# Power.net
KiCad netlist of a schematic drawn in Altium Designer
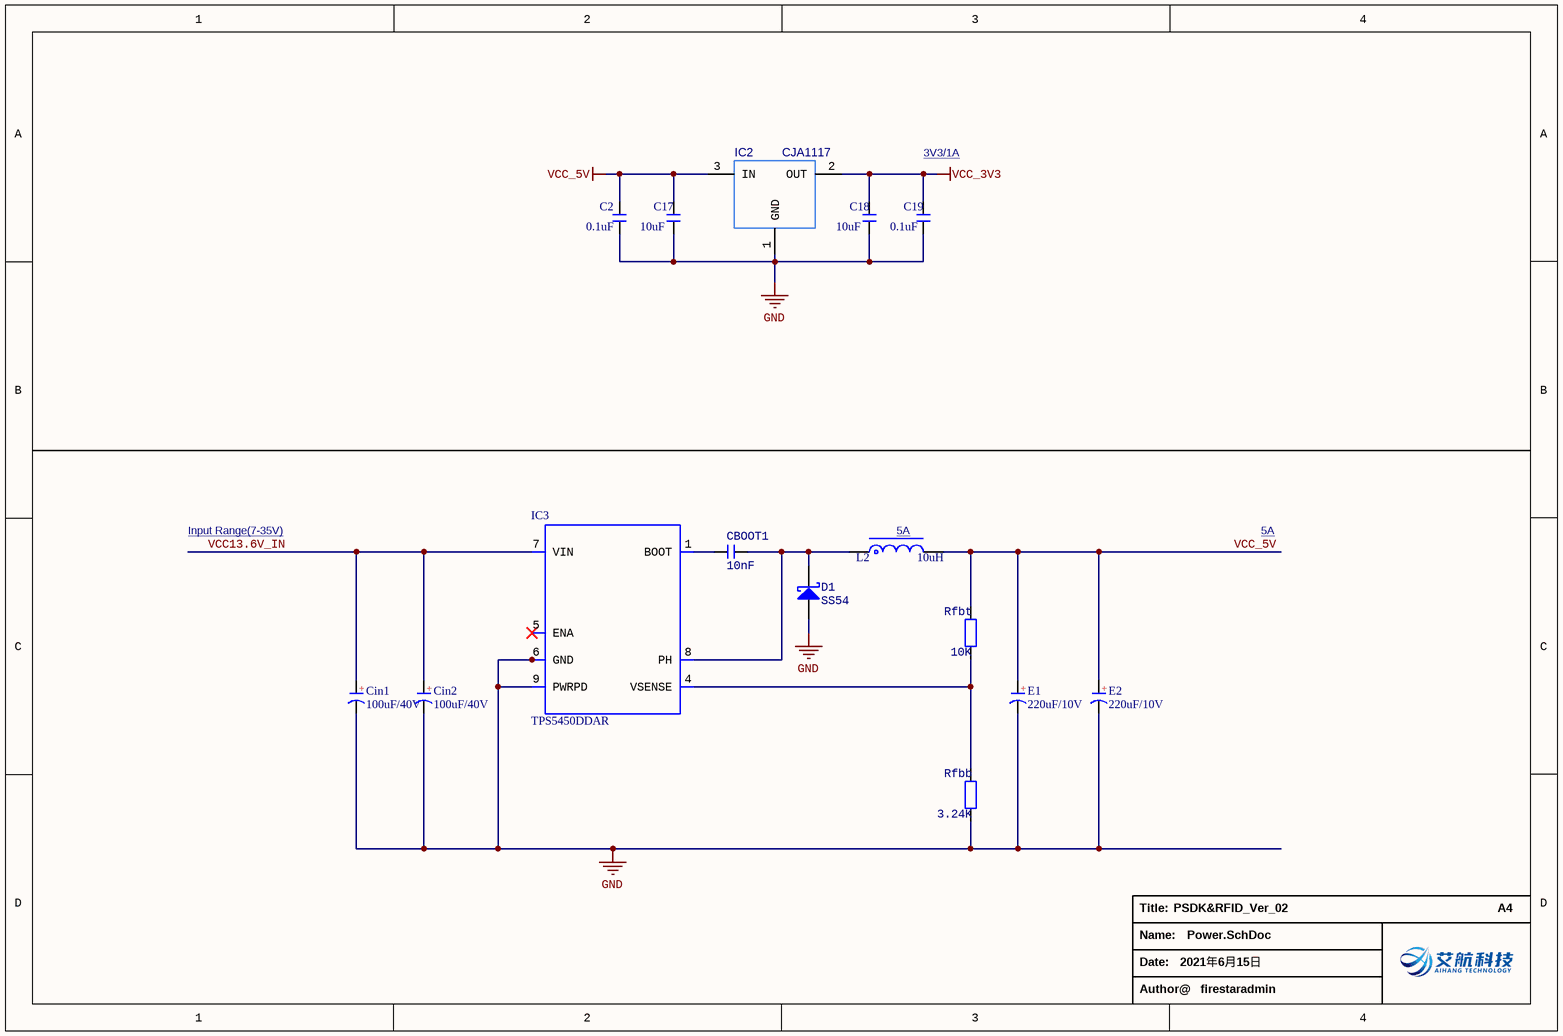
[diagram p0: Power.SchDoc]

(export (version "E")
  (design (tool "Eeschema 10.0.6"))
  (components
    (comp (ref "C2")
      (value "0.1uF")
      (footprint "C 0603_L")
      (description "无极性贴片电容")
      (fields (field (name "版权归属") "源创客"))
      (libsource (lib "altium-import") (part "root_1_C_"))
    )
    (comp (ref "C17")
      (value "10uF")
      (footprint "C 0805_L")
      (description "无极性贴片电容")
      (fields (field (name "版权归属") "源创客"))
      (libsource (lib "altium-import") (part "root_1_C_"))
    )
    (comp (ref "C18")
      (value "10uF")
      (footprint "C 0805_L")
      (description "无极性贴片电容")
      (fields (field (name "版权归属") "源创客"))
      (libsource (lib "altium-import") (part "root_1_C_"))
    )
    (comp (ref "C19")
      (value "0.1uF")
      (footprint "C 0603_L")
      (description "无极性贴片电容")
      (fields (field (name "版权归属") "源创客"))
      (libsource (lib "altium-import") (part "root_1_C_"))
    )
    (comp (ref "CBOOT1")
      (value "10nF")
      (footprint "C 0603_L")
      (description "无极性贴片电容")
      (fields (field (name "版权归属") "源创客"))
      (libsource (lib "SCH-电阻-电容-电感") (part "C"))
    )
    (comp (ref "Cin1")
      (value "100uF/40V")
      (footprint "CM D(6.3*7.7)")
      (description "贴片电解电容")
      (fields (field (name "版权归属") "源创客"))
      (libsource (lib "SCH-电阻-电容-电感") (part "C-CM"))
    )
    (comp (ref "Cin2")
      (value "100uF/40V")
      (footprint "CM D(6.3*7.7)")
      (description "贴片电解电容")
      (fields (field (name "版权归属") "源创客"))
      (libsource (lib "SCH-电阻-电容-电感") (part "C-CM"))
    )
    (comp (ref "D1")
      (value "SS54")
      (footprint "SMC")
      (description "肖特基二极管")
      (libsource (lib "SCH-二极管-整流桥") (part "SS54"))
    )
    (comp (ref "E1")
      (value "220uF/10V")
      (footprint "CD D(7343)")
      (description "贴片钽电容")
      (fields (field (name "版权归属") "源创客"))
      (libsource (lib "SCH-电阻-电容-电感") (part "C-CD"))
    )
    (comp (ref "E2")
      (value "220uF/10V")
      (footprint "CD D(7343)")
      (description "贴片钽电容")
      (fields (field (name "版权归属") "源创客"))
      (libsource (lib "SCH-电阻-电容-电感") (part "C-CD"))
    )
    (comp (ref "IC2")
      (value "CJA1117")
      (footprint "SOT89_M")
      (description "线性稳压器(LDO) SOT89  CJA1117B-3.3 : 最大输入电压  15V ; 3.3V @ 1A")
      (libsource (lib "SCH-电源类芯片") (part "CJA1117"))
    )
    (comp (ref "IC3")
      (value "TPS5450")
      (footprint "ESOP8_N")
      (fields
        (field (name "MANUFACTURER PART NUMBER") "TPS5450DDA")
        (field (name "PACKAGEREFERENCE") "TPS5450DDAR")
      )
      (libsource (lib "SCH-电源类芯片") (part "TPS5450"))
    )
    (comp (ref "L2")
      (value "10uH")
      (footprint "L-SMD-1040")
      (description "贴片功率电感")
      (fields (field (name "版权归属") "源创客"))
      (libsource (lib "SCH-电阻-电容-电感") (part "L-CD"))
    )
    (comp (ref "Rfbb")
      (value "3.24K")
      (footprint "R 0603_L")
      (description "贴片电阻")
      (fields (field (name "版权归属") "源创客"))
      (libsource (lib "SCH-电阻-电容-电感") (part "R"))
    )
    (comp (ref "Rfbt")
      (value "10K")
      (footprint "R 0603_L")
      (description "贴片电阻")
      (fields (field (name "版权归属") "源创客"))
      (libsource (lib "SCH-电阻-电容-电感") (part "R"))
    )
  )
  (nets
    (net (code "1") (name "/VCC13.6V_IN") (class "Default")
      (node (ref "Cin1") (pin "1") (pinfunction "A_1") (pintype "passive"))
      (node (ref "Cin2") (pin "1") (pinfunction "A_1") (pintype "passive"))
      (node (ref "IC3") (pin "7") (pinfunction "VIN_7") (pintype "passive"))
    )
    (net (code "2") (name "GND") (class "Default")
      (node (ref "C17") (pin "1") (pinfunction "1_1") (pintype "passive"))
      (node (ref "C18") (pin "1") (pinfunction "1_1") (pintype "passive"))
      (node (ref "C19") (pin "1") (pinfunction "1_1") (pintype "passive"))
      (node (ref "C2") (pin "1") (pinfunction "1_1") (pintype "passive"))
      (node (ref "Cin1") (pin "2") (pinfunction "K_2") (pintype "passive"))
      (node (ref "Cin2") (pin "2") (pinfunction "K_2") (pintype "passive"))
      (node (ref "D1") (pin "1") (pinfunction "A_1") (pintype "passive"))
      (node (ref "E1") (pin "2") (pinfunction "K_2") (pintype "passive"))
      (node (ref "E2") (pin "2") (pinfunction "K_2") (pintype "passive"))
      (node (ref "IC2") (pin "1") (pinfunction "GND_1") (pintype "passive"))
      (node (ref "IC3") (pin "2") (pinfunction "NC_2") (pintype "passive"))
      (node (ref "IC3") (pin "3") (pinfunction "NC_3") (pintype "passive"))
      (node (ref "IC3") (pin "6") (pinfunction "GND_6") (pintype "passive"))
      (node (ref "IC3") (pin "9") (pinfunction "PWRPD_9") (pintype "passive"))
      (node (ref "Rfbb") (pin "1") (pinfunction "1_1") (pintype "passive"))
    )
    (net (code "3") (name "Net-(D1-K)") (class "Default")
      (node (ref "CBOOT1") (pin "2") (pinfunction "2_2") (pintype "passive"))
      (node (ref "D1") (pin "2") (pinfunction "K_2") (pintype "passive"))
      (node (ref "IC3") (pin "8") (pinfunction "PH_8") (pintype "passive"))
      (node (ref "L2") (pin "1") (pinfunction "1_1") (pintype "passive"))
    )
    (net (code "4") (name "Net-(IC3-BOOT)") (class "Default")
      (node (ref "CBOOT1") (pin "1") (pinfunction "1_1") (pintype "passive"))
      (node (ref "IC3") (pin "1") (pinfunction "BOOT_1") (pintype "passive"))
    )
    (net (code "5") (name "Net-(IC3-VSENSE)") (class "Default")
      (node (ref "IC3") (pin "4") (pinfunction "VSENSE_4") (pintype "passive"))
      (node (ref "Rfbb") (pin "2") (pinfunction "2_2") (pintype "passive"))
      (node (ref "Rfbt") (pin "1") (pinfunction "1_1") (pintype "passive"))
    )
    (net (code "6") (name "VCC_3V3") (class "Default")
      (node (ref "C18") (pin "2") (pinfunction "2_2") (pintype "passive"))
      (node (ref "C19") (pin "2") (pinfunction "2_2") (pintype "passive"))
      (node (ref "IC2") (pin "2") (pinfunction "OUT_2") (pintype "passive"))
    )
    (net (code "7") (name "VCC_5V") (class "Default")
      (node (ref "C17") (pin "2") (pinfunction "2_2") (pintype "passive"))
      (node (ref "C2") (pin "2") (pinfunction "2_2") (pintype "passive"))
      (node (ref "E1") (pin "1") (pinfunction "A_1") (pintype "passive"))
      (node (ref "E2") (pin "1") (pinfunction "A_1") (pintype "passive"))
      (node (ref "IC2") (pin "3") (pinfunction "IN_3") (pintype "passive"))
      (node (ref "L2") (pin "2") (pinfunction "2_2") (pintype "passive"))
      (node (ref "Rfbt") (pin "2") (pinfunction "2_2") (pintype "passive"))
    )
    (net (code "8") (name "unconnected-(IC3-ENA-Pad5)") (class "Default")
      (node (ref "IC3") (pin "5") (pinfunction "ENA_5") (pintype "passive+no_connect"))
    )
  )
)
